# 16_WIFI_BT-1T1R.net
KiCad netlist of a schematic drawn in Altium Designer
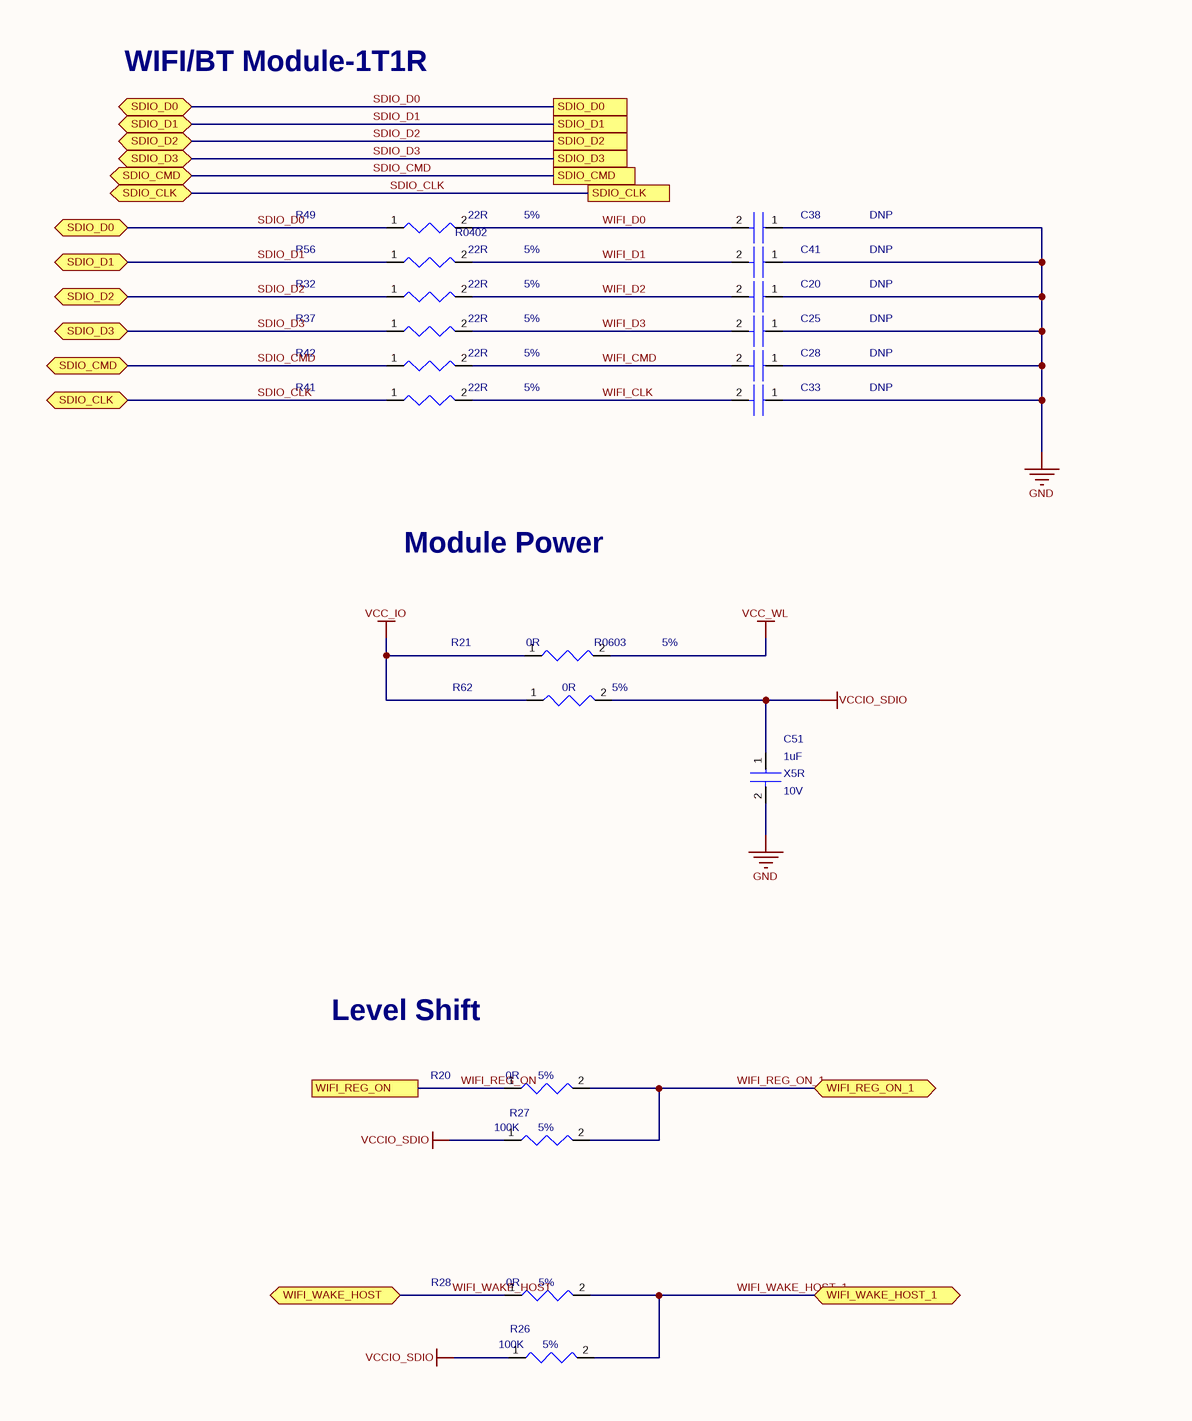
[diagram p0: 16_WIFI_BT-1T1R.SchDoc, left]
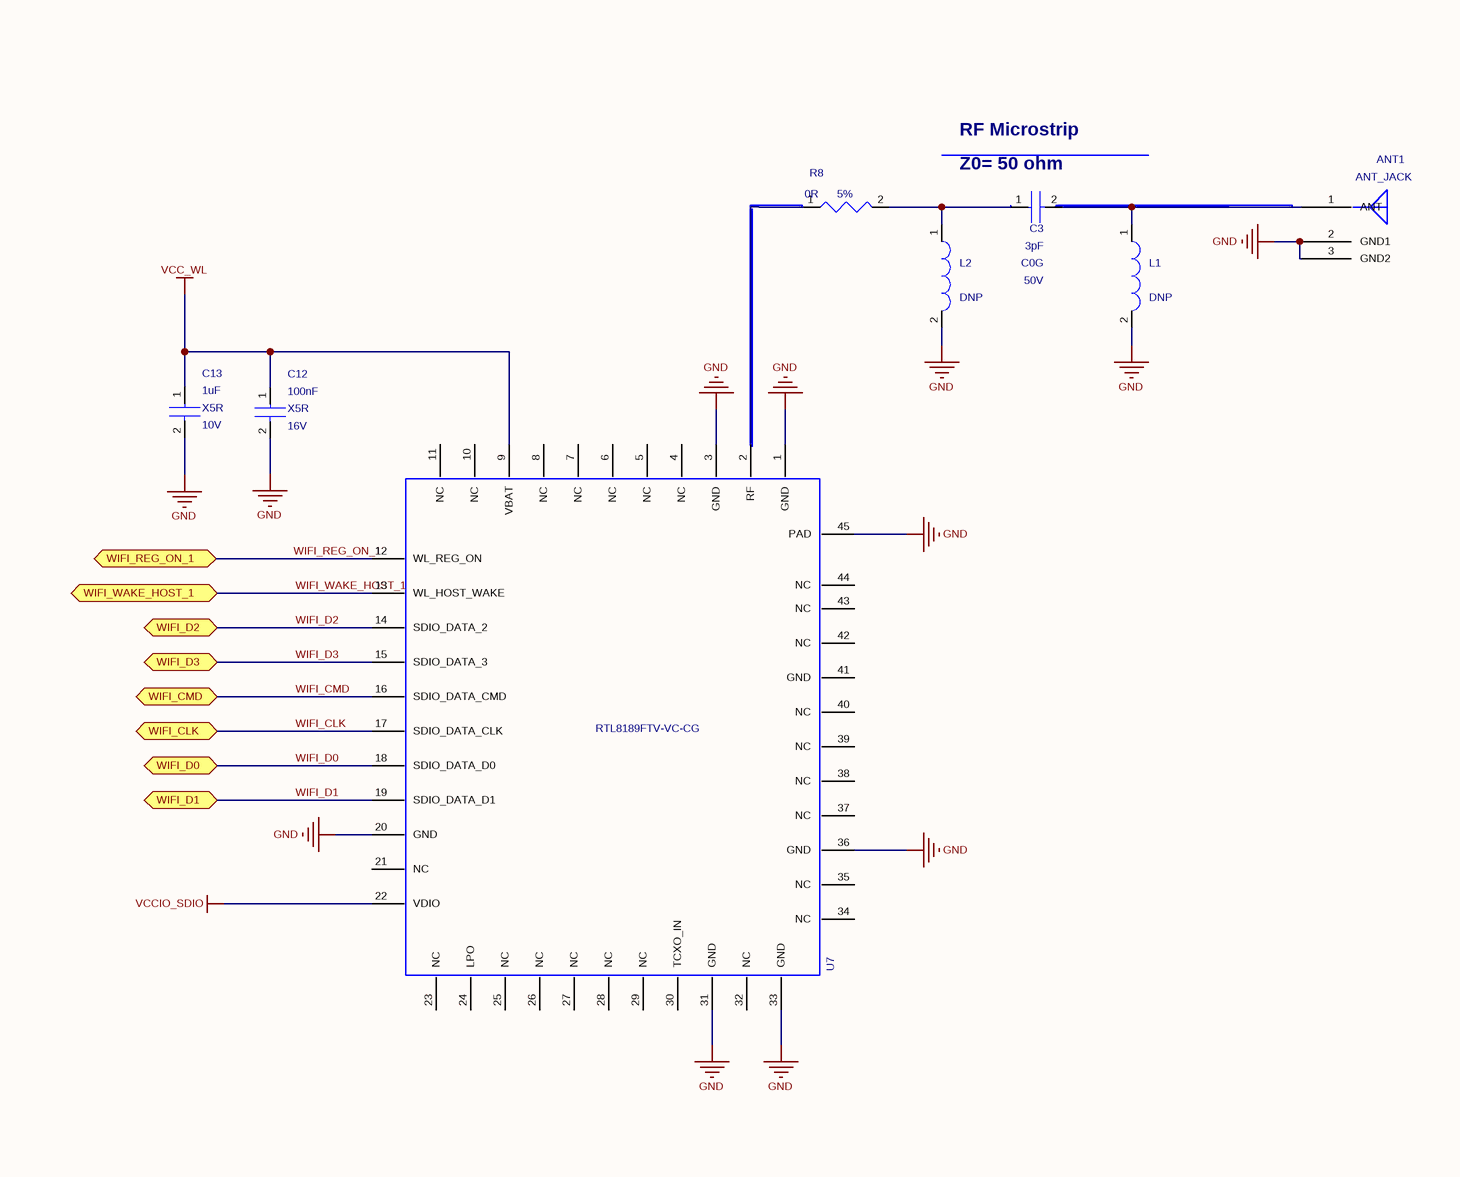
[diagram p1: 16_WIFI_BT-1T1R.SchDoc, right]

(export (version "E")
  (design (tool "Eeschema 10.0.6"))
  (components
    (comp (ref "ANT1")
      (value "ANT_1P2G")
      (footprint "ANT_JACK")
      (description "焊接式WIFI天线座，单频")
      (fields (field (name "PCB DECAL") "ANT_JACK") (field (name "CREATED_BY") "JJJ"))
      (libsource (lib "*") (part "ANT_1P2G"))
    )
    (comp (ref "C3")
      (value "3pF")
      (footprint "C0402")
      (description "cap,3.00pF,+/-0.1,50V,C0G,C0402")
      (fields
        (field (name "DIELECTRIC") "C0G")
        (field (name "VOLTAGE") "50V")
        (field (name "TOLERANCE") "+/-0.1pF")
        (field (name "MANUFACTURER") "TDK")
        (field (name "CREATED_BY") "JJJ")
      )
      (libsource (lib "*") (part "CAP_NP_2"))
    )
    (comp (ref "C12")
      (value "100nF")
      (footprint "C0402")
      (description "cap,100.00nF,+/-10%,16V,X5R,C0402")
      (fields
        (field (name "DIELECTRIC") "X5R")
        (field (name "TOLERANCE") "10%")
        (field (name "MANUFACTURER") "TDK")
        (field (name "VOLTAGE") "16V")
        (field (name "CREATED_BY") "JJJ")
      )
      (libsource (lib "*") (part "CAP_NP_2"))
    )
    (comp (ref "C13")
      (value "1uF")
      (footprint "C0402")
      (description "cap,1.00uF,+/-10%,10V,X5R,C0402")
      (fields
        (field (name "DIELECTRIC") "X5R")
        (field (name "VOLTAGE") "10V")
        (field (name "TOLERANCE") "10%")
        (field (name "MANUFACTURER") "TDK")
        (field (name "CREATED_BY") "JJJ")
      )
      (libsource (lib "*") (part "CAP_NP_2"))
    )
    (comp (ref "C20")
      (value "DNP")
      (footprint "C0402")
      (description "Did Not Place.")
      (fields (field (name "Comment") "CAP_NP_2") (field (name "CREATED_BY") "JJJ"))
      (libsource (lib "*") (part "CAP_NP_2"))
    )
    (comp (ref "C25")
      (value "DNP")
      (footprint "C0402")
      (description "Did Not Place.")
      (fields (field (name "Comment") "CAP_NP_2") (field (name "CREATED_BY") "JJJ"))
      (libsource (lib "*") (part "CAP_NP_2"))
    )
    (comp (ref "C28")
      (value "DNP")
      (footprint "C0402")
      (description "Did Not Place.")
      (fields (field (name "Comment") "CAP_NP_2") (field (name "CREATED_BY") "JJJ"))
      (libsource (lib "*") (part "CAP_NP_2"))
    )
    (comp (ref "C33")
      (value "DNP")
      (footprint "C0402")
      (description "Did Not Place.")
      (fields (field (name "Comment") "CAP_NP_2") (field (name "CREATED_BY") "JJJ"))
      (libsource (lib "*") (part "CAP_NP_2"))
    )
    (comp (ref "C38")
      (value "DNP")
      (footprint "C0402")
      (description "Did Not Place.")
      (fields (field (name "Comment") "CAP_NP_2") (field (name "CREATED_BY") "JJJ"))
      (libsource (lib "*") (part "CAP_NP_2"))
    )
    (comp (ref "C41")
      (value "DNP")
      (footprint "C0402")
      (description "Did Not Place.")
      (fields (field (name "Comment") "CAP_NP_2") (field (name "CREATED_BY") "JJJ"))
      (libsource (lib "*") (part "CAP_NP_2"))
    )
    (comp (ref "C51")
      (value "1uF")
      (footprint "C0402")
      (description "cap,1.00uF,+/-10%,10V,X5R,C0402")
      (fields
        (field (name "VOLTAGE") "10V")
        (field (name "MANUFACTURER") "TDK")
        (field (name "TOLERANCE") "10%")
        (field (name "DIELECTRIC") "X5R")
        (field (name "CREATED_BY") "JJJ")
      )
      (libsource (lib "*") (part "CAP_NP_2"))
    )
    (comp (ref "L1")
      (value "DNP")
      (footprint "L0402")
      (description "Did Not Place.")
      (fields (field (name "Comment") "INDUCTOR") (field (name "CREATED_BY") "JJJ"))
      (libsource (lib "*") (part "INDUCTOR"))
    )
    (comp (ref "L2")
      (value "DNP")
      (footprint "L0402")
      (description "Did Not Place.")
      (fields (field (name "Comment") "INDUCTOR") (field (name "CREATED_BY") "JJJ"))
      (libsource (lib "*") (part "INDUCTOR"))
    )
    (comp (ref "R8")
      (value "0R")
      (footprint "R0402")
      (description "?用厚膜电阻,0R,+/-5%,R0402,1/16W.")
      (fields
        (field (name "TOLERANCE") "5%")
        (field (name "MANUFACTURER") "YAGEO")
        (field (name "Comment") "RESISTOR")
        (field (name "CREATED_BY") "YTL")
      )
      (libsource (lib "*") (part "RESISTOR"))
    )
    (comp (ref "R20")
      (value "0R")
      (footprint "R0402")
      (description "?用厚膜电阻,10K,+/-5%,R0402,1/16W.")
      (fields
        (field (name "MANUFACTURER") "YAGEO")
        (field (name "TOLERANCE") "5%")
        (field (name "Comment") "RESISTOR")
        (field (name "CREATED_BY") "YTL")
      )
      (libsource (lib "*") (part "RESISTOR"))
    )
    (comp (ref "R21")
      (value "0R")
      (footprint "R0603")
      (description "?用厚膜电阻,0R,+/-5%,R0603,1/10W.")
      (fields
        (field (name "PCB DECAL") "R0603")
        (field (name "MANUFACTURER") "YAGEO")
        (field (name "TOLERANCE") "5%")
        (field (name "Comment") "RESISTOR")
        (field (name "CREATED_BY") "YTL")
      )
      (libsource (lib "*") (part "RESISTOR"))
    )
    (comp (ref "R26")
      (value "100K")
      (footprint "R0402")
      (description "?用厚膜电阻,100K,+/-5%,R0402,1/16W.")
      (fields
        (field (name "TOLERANCE") "5%")
        (field (name "MANUFACTURER") "YAGEO")
        (field (name "Comment") "RESISTOR")
        (field (name "CREATED_BY") "YTL")
      )
      (libsource (lib "*") (part "RESISTOR"))
    )
    (comp (ref "R27")
      (value "100K")
      (footprint "R0402")
      (description "?用厚膜电阻,100K,+/-5%,R0402,1/16W.")
      (fields
        (field (name "TOLERANCE") "5%")
        (field (name "MANUFACTURER") "YAGEO")
        (field (name "Comment") "RESISTOR")
        (field (name "CREATED_BY") "YTL")
      )
      (libsource (lib "*") (part "RESISTOR"))
    )
    (comp (ref "R28")
      (value "0R")
      (footprint "R0402")
      (description "?用厚膜电阻,10K,+/-5%,R0402,1/16W.")
      (fields
        (field (name "MANUFACTURER") "YAGEO")
        (field (name "TOLERANCE") "5%")
        (field (name "Comment") "RESISTOR")
        (field (name "CREATED_BY") "YTL")
      )
      (libsource (lib "*") (part "RESISTOR"))
    )
    (comp (ref "R32")
      (value "22R")
      (footprint "R0402")
      (description "?用厚膜电阻,22R,+/-5%,R0402,1/16W.")
      (fields
        (field (name "MANUFACTURER") "YAGEO")
        (field (name "TOLERANCE") "5%")
        (field (name "Comment") "RESISTOR")
        (field (name "CREATED_BY") "YTL")
      )
      (libsource (lib "*") (part "RESISTOR"))
    )
    (comp (ref "R37")
      (value "22R")
      (footprint "R0402")
      (description "?用厚膜电阻,22R,+/-5%,R0402,1/16W.")
      (fields
        (field (name "MANUFACTURER") "YAGEO")
        (field (name "TOLERANCE") "5%")
        (field (name "Comment") "RESISTOR")
        (field (name "CREATED_BY") "YTL")
      )
      (libsource (lib "*") (part "RESISTOR"))
    )
    (comp (ref "R41")
      (value "22R")
      (footprint "R0402")
      (description "?用厚膜电阻,22R,+/-5%,R0402,1/16W.")
      (fields
        (field (name "MANUFACTURER") "YAGEO")
        (field (name "TOLERANCE") "5%")
        (field (name "Comment") "RESISTOR")
        (field (name "CREATED_BY") "YTL")
      )
      (libsource (lib "*") (part "RESISTOR"))
    )
    (comp (ref "R42")
      (value "22R")
      (footprint "R0402")
      (description "?用厚膜电阻,22R,+/-5%,R0402,1/16W.")
      (fields
        (field (name "MANUFACTURER") "YAGEO")
        (field (name "TOLERANCE") "5%")
        (field (name "Comment") "RESISTOR")
        (field (name "CREATED_BY") "YTL")
      )
      (libsource (lib "*") (part "RESISTOR"))
    )
    (comp (ref "R49")
      (value "22R")
      (footprint "R0402")
      (description "?用厚膜电阻,22R,+/-5%,R0402,1/16W.")
      (fields
        (field (name "PCB DECAL") "R0402")
        (field (name "TOLERANCE") "5%")
        (field (name "MANUFACTURER") "YAGEO")
        (field (name "Comment") "RESISTOR")
        (field (name "CREATED_BY") "YTL")
      )
      (libsource (lib "*") (part "RESISTOR"))
    )
    (comp (ref "R56")
      (value "22R")
      (footprint "R0402")
      (description "?用厚膜电阻,22R,+/-5%,R0402,1/16W.")
      (fields
        (field (name "MANUFACTURER") "YAGEO")
        (field (name "TOLERANCE") "5%")
        (field (name "Comment") "RESISTOR")
        (field (name "CREATED_BY") "YTL")
      )
      (libsource (lib "*") (part "RESISTOR"))
    )
    (comp (ref "R62")
      (value "0R")
      (footprint "R0603")
      (description "?用厚膜电阻,0R,+/-5%,R0402,1/16W.")
      (fields
        (field (name "MANUFACTURER") "YAGEO")
        (field (name "TOLERANCE") "5%")
        (field (name "Comment") "RESISTOR")
        (field (name "CREATED_BY") "YTL")
      )
      (libsource (lib "*") (part "RESISTOR"))
    )
    (comp (ref "U7")
      (value "RTL8189FTV-VC-CG")
      (footprint "RTL8189FTV")
      (description "IEEE 802.11 b/g/n 2.4GHz 1T1R SDIO LGA Module")
      (libsource (lib "*") (part "RTL8189FTV-VC-CG"))
    )
  )
  (nets
    (net (code "1") (name "/SDIO_CLK") (class "Default")
      (node (ref "R41") (pin "1") (pinfunction "1_1") (pintype "passive"))
    )
    (net (code "2") (name "/SDIO_CMD") (class "Default")
      (node (ref "R42") (pin "1") (pinfunction "1_1") (pintype "passive"))
    )
    (net (code "3") (name "/SDIO_D0") (class "Default")
      (node (ref "R49") (pin "1") (pinfunction "1_1") (pintype "passive"))
    )
    (net (code "4") (name "/SDIO_D1") (class "Default")
      (node (ref "R56") (pin "1") (pinfunction "1_1") (pintype "passive"))
    )
    (net (code "5") (name "/SDIO_D2") (class "Default")
      (node (ref "R32") (pin "1") (pinfunction "1_1") (pintype "passive"))
    )
    (net (code "6") (name "/SDIO_D3") (class "Default")
      (node (ref "R37") (pin "1") (pinfunction "1_1") (pintype "passive"))
    )
    (net (code "7") (name "/WIFI_CLK") (class "Default")
      (node (ref "C33") (pin "2") (pinfunction "2_2") (pintype "passive"))
      (node (ref "R41") (pin "2") (pinfunction "2_2") (pintype "passive"))
      (node (ref "U7") (pin "17") (pinfunction "SDIO_DATA_CLK_17") (pintype "passive"))
    )
    (net (code "8") (name "/WIFI_CMD") (class "Default")
      (node (ref "C28") (pin "2") (pinfunction "2_2") (pintype "passive"))
      (node (ref "R42") (pin "2") (pinfunction "2_2") (pintype "passive"))
      (node (ref "U7") (pin "16") (pinfunction "SDIO_DATA_CMD_16") (pintype "passive"))
    )
    (net (code "9") (name "/WIFI_D0") (class "Default")
      (node (ref "C38") (pin "2") (pinfunction "2_2") (pintype "passive"))
      (node (ref "R49") (pin "2") (pinfunction "2_2") (pintype "passive"))
      (node (ref "U7") (pin "18") (pinfunction "SDIO_DATA_D0_18") (pintype "passive"))
    )
    (net (code "10") (name "/WIFI_D1") (class "Default")
      (node (ref "C41") (pin "2") (pinfunction "2_2") (pintype "passive"))
      (node (ref "R56") (pin "2") (pinfunction "2_2") (pintype "passive"))
      (node (ref "U7") (pin "19") (pinfunction "SDIO_DATA_D1_19") (pintype "passive"))
    )
    (net (code "11") (name "/WIFI_D2") (class "Default")
      (node (ref "C20") (pin "2") (pinfunction "2_2") (pintype "passive"))
      (node (ref "R32") (pin "2") (pinfunction "2_2") (pintype "passive"))
      (node (ref "U7") (pin "14") (pinfunction "SDIO_DATA_2_14") (pintype "passive"))
    )
    (net (code "12") (name "/WIFI_D3") (class "Default")
      (node (ref "C25") (pin "2") (pinfunction "2_2") (pintype "passive"))
      (node (ref "R37") (pin "2") (pinfunction "2_2") (pintype "passive"))
      (node (ref "U7") (pin "15") (pinfunction "SDIO_DATA_3_15") (pintype "passive"))
    )
    (net (code "13") (name "/WIFI_REG_ON") (class "Default")
      (node (ref "R20") (pin "1") (pinfunction "1_1") (pintype "passive"))
    )
    (net (code "14") (name "/WIFI_REG_ON_1") (class "Default")
      (node (ref "R20") (pin "2") (pinfunction "2_2") (pintype "passive"))
      (node (ref "R27") (pin "2") (pinfunction "2_2") (pintype "passive"))
      (node (ref "U7") (pin "12") (pinfunction "WL_REG_ON_12") (pintype "passive"))
    )
    (net (code "15") (name "/WIFI_WAKE_HOST") (class "Default")
      (node (ref "R28") (pin "1") (pinfunction "1_1") (pintype "passive"))
    )
    (net (code "16") (name "/WIFI_WAKE_HOST_1") (class "Default")
      (node (ref "R26") (pin "2") (pinfunction "2_2") (pintype "passive"))
      (node (ref "R28") (pin "2") (pinfunction "2_2") (pintype "passive"))
      (node (ref "U7") (pin "13") (pinfunction "WL_HOST_WAKE_13") (pintype "passive"))
    )
    (net (code "17") (name "GND") (class "Default")
      (node (ref "ANT1") (pin "2") (pinfunction "GND1_2") (pintype "passive"))
      (node (ref "ANT1") (pin "3") (pinfunction "GND2_3") (pintype "passive"))
      (node (ref "C12") (pin "2") (pinfunction "2_2") (pintype "passive"))
      (node (ref "C13") (pin "2") (pinfunction "2_2") (pintype "passive"))
      (node (ref "C20") (pin "1") (pinfunction "1_1") (pintype "passive"))
      (node (ref "C25") (pin "1") (pinfunction "1_1") (pintype "passive"))
      (node (ref "C28") (pin "1") (pinfunction "1_1") (pintype "passive"))
      (node (ref "C33") (pin "1") (pinfunction "1_1") (pintype "passive"))
      (node (ref "C38") (pin "1") (pinfunction "1_1") (pintype "passive"))
      (node (ref "C41") (pin "1") (pinfunction "1_1") (pintype "passive"))
      (node (ref "C51") (pin "2") (pinfunction "2_2") (pintype "passive"))
      (node (ref "L1") (pin "2") (pinfunction "2_2") (pintype "passive"))
      (node (ref "L2") (pin "2") (pinfunction "2_2") (pintype "passive"))
      (node (ref "U7") (pin "1") (pinfunction "GND_1") (pintype "passive"))
      (node (ref "U7") (pin "20") (pinfunction "GND_20") (pintype "passive"))
      (node (ref "U7") (pin "3") (pinfunction "GND_3") (pintype "passive"))
      (node (ref "U7") (pin "31") (pinfunction "GND_31") (pintype "passive"))
      (node (ref "U7") (pin "33") (pinfunction "GND_33") (pintype "passive"))
      (node (ref "U7") (pin "36") (pinfunction "GND_36") (pintype "passive"))
      (node (ref "U7") (pin "45") (pinfunction "PAD_45") (pintype "passive"))
    )
    (net (code "18") (name "Net-(ANT1-ANT)") (class "Default")
      (node (ref "ANT1") (pin "1") (pinfunction "ANT_1") (pintype "passive"))
      (node (ref "C3") (pin "2") (pinfunction "2_2") (pintype "passive"))
      (node (ref "L1") (pin "1") (pinfunction "1_1") (pintype "passive"))
    )
    (net (code "19") (name "Net-(C3-Pad1)") (class "Default")
      (node (ref "C3") (pin "1") (pinfunction "1_1") (pintype "passive"))
      (node (ref "L2") (pin "1") (pinfunction "1_1") (pintype "passive"))
      (node (ref "R8") (pin "2") (pinfunction "2_2") (pintype "passive"))
    )
    (net (code "20") (name "Net-(U7-RF)") (class "Default")
      (node (ref "R8") (pin "1") (pinfunction "1_1") (pintype "passive"))
      (node (ref "U7") (pin "2") (pinfunction "RF_2") (pintype "passive"))
    )
    (net (code "21") (name "VCCIO_SDIO") (class "Default")
      (node (ref "C51") (pin "1") (pinfunction "1_1") (pintype "passive"))
      (node (ref "R26") (pin "1") (pinfunction "1_1") (pintype "passive"))
      (node (ref "R27") (pin "1") (pinfunction "1_1") (pintype "passive"))
      (node (ref "R62") (pin "2") (pinfunction "2_2") (pintype "passive"))
      (node (ref "U7") (pin "22") (pinfunction "VDIO_22") (pintype "passive"))
    )
    (net (code "22") (name "VCC_IO") (class "Default")
      (node (ref "R21") (pin "1") (pinfunction "1_1") (pintype "passive"))
      (node (ref "R62") (pin "1") (pinfunction "1_1") (pintype "passive"))
    )
    (net (code "23") (name "VCC_WL") (class "Default")
      (node (ref "C12") (pin "1") (pinfunction "1_1") (pintype "passive"))
      (node (ref "C13") (pin "1") (pinfunction "1_1") (pintype "passive"))
      (node (ref "R21") (pin "2") (pinfunction "2_2") (pintype "passive"))
      (node (ref "U7") (pin "9") (pinfunction "VBAT_9") (pintype "passive"))
    )
    (net (code "24") (name "unconnected-(U7-GND-Pad41)") (class "Default")
      (node (ref "U7") (pin "41") (pinfunction "GND_41") (pintype "passive"))
    )
    (net (code "25") (name "unconnected-(U7-LPO-Pad24)") (class "Default")
      (node (ref "U7") (pin "24") (pinfunction "LPO_24") (pintype "passive"))
    )
    (net (code "26") (name "unconnected-(U7-NC-Pad4)") (class "Default")
      (node (ref "U7") (pin "4") (pinfunction "NC_4") (pintype "passive"))
    )
    (net (code "27") (name "unconnected-(U7-NC-Pad5)") (class "Default")
      (node (ref "U7") (pin "5") (pinfunction "NC_5") (pintype "passive"))
    )
    (net (code "28") (name "unconnected-(U7-NC-Pad6)") (class "Default")
      (node (ref "U7") (pin "6") (pinfunction "NC_6") (pintype "passive"))
    )
    (net (code "29") (name "unconnected-(U7-NC-Pad7)") (class "Default")
      (node (ref "U7") (pin "7") (pinfunction "NC_7") (pintype "passive"))
    )
    (net (code "30") (name "unconnected-(U7-NC-Pad8)") (class "Default")
      (node (ref "U7") (pin "8") (pinfunction "NC_8") (pintype "passive"))
    )
    (net (code "31") (name "unconnected-(U7-NC-Pad10)") (class "Default")
      (node (ref "U7") (pin "10") (pinfunction "NC_10") (pintype "passive"))
    )
    (net (code "32") (name "unconnected-(U7-NC-Pad11)") (class "Default")
      (node (ref "U7") (pin "11") (pinfunction "NC_11") (pintype "passive"))
    )
    (net (code "33") (name "unconnected-(U7-NC-Pad21)") (class "Default")
      (node (ref "U7") (pin "21") (pinfunction "NC_21") (pintype "passive"))
    )
    (net (code "34") (name "unconnected-(U7-NC-Pad23)") (class "Default")
      (node (ref "U7") (pin "23") (pinfunction "NC_23") (pintype "passive"))
    )
    (net (code "35") (name "unconnected-(U7-NC-Pad25)") (class "Default")
      (node (ref "U7") (pin "25") (pinfunction "NC_25") (pintype "passive"))
    )
    (net (code "36") (name "unconnected-(U7-NC-Pad26)") (class "Default")
      (node (ref "U7") (pin "26") (pinfunction "NC_26") (pintype "passive"))
    )
    (net (code "37") (name "unconnected-(U7-NC-Pad27)") (class "Default")
      (node (ref "U7") (pin "27") (pinfunction "NC_27") (pintype "passive"))
    )
    (net (code "38") (name "unconnected-(U7-NC-Pad28)") (class "Default")
      (node (ref "U7") (pin "28") (pinfunction "NC_28") (pintype "passive"))
    )
    (net (code "39") (name "unconnected-(U7-NC-Pad29)") (class "Default")
      (node (ref "U7") (pin "29") (pinfunction "NC_29") (pintype "passive"))
    )
    (net (code "40") (name "unconnected-(U7-NC-Pad32)") (class "Default")
      (node (ref "U7") (pin "32") (pinfunction "NC_32") (pintype "passive"))
    )
    (net (code "41") (name "unconnected-(U7-NC-Pad34)") (class "Default")
      (node (ref "U7") (pin "34") (pinfunction "NC_34") (pintype "passive"))
    )
    (net (code "42") (name "unconnected-(U7-NC-Pad35)") (class "Default")
      (node (ref "U7") (pin "35") (pinfunction "NC_35") (pintype "passive"))
    )
    (net (code "43") (name "unconnected-(U7-NC-Pad37)") (class "Default")
      (node (ref "U7") (pin "37") (pinfunction "NC_37") (pintype "passive"))
    )
    (net (code "44") (name "unconnected-(U7-NC-Pad38)") (class "Default")
      (node (ref "U7") (pin "38") (pinfunction "NC_38") (pintype "passive"))
    )
    (net (code "45") (name "unconnected-(U7-NC-Pad39)") (class "Default")
      (node (ref "U7") (pin "39") (pinfunction "NC_39") (pintype "passive"))
    )
    (net (code "46") (name "unconnected-(U7-NC-Pad40)") (class "Default")
      (node (ref "U7") (pin "40") (pinfunction "NC_40") (pintype "passive"))
    )
    (net (code "47") (name "unconnected-(U7-NC-Pad42)") (class "Default")
      (node (ref "U7") (pin "42") (pinfunction "NC_42") (pintype "passive"))
    )
    (net (code "48") (name "unconnected-(U7-NC-Pad43)") (class "Default")
      (node (ref "U7") (pin "43") (pinfunction "NC_43") (pintype "passive"))
    )
    (net (code "49") (name "unconnected-(U7-NC-Pad44)") (class "Default")
      (node (ref "U7") (pin "44") (pinfunction "NC_44") (pintype "passive"))
    )
    (net (code "50") (name "unconnected-(U7-TCXO_IN-Pad30)") (class "Default")
      (node (ref "U7") (pin "30") (pinfunction "TCXO_IN_30") (pintype "passive"))
    )
  )
)
